# NCV1117STAT3G.net
KiCad netlist of a schematic drawn in Altium Designer
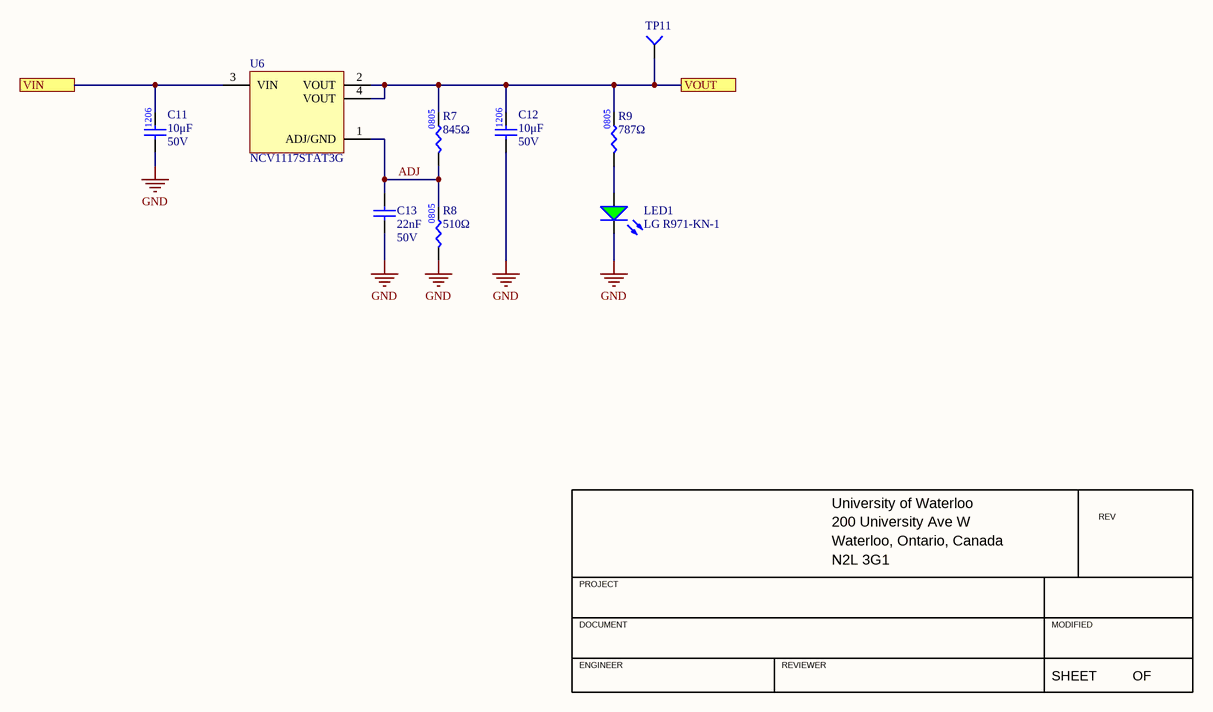
[diagram p0: NCV1117STAT3G.SchDoc]

(export (version "E")
  (design (tool "Eeschema 10.0.6"))
  (components
    (comp (ref "C11")
      (value "10μF")
      (footprint "CAP1206")
      (description "CAP CER 10UF 50V X5R 1206")
      (fields (field (name "VOLTAGE RATING") "50V") (field (name "Comment") "CAP_10uF_50V_1206"))
      (libsource (lib "UWRT_Schematic_Library_2020") (part "CAP_10uF_50V_1206"))
    )
    (comp (ref "C12")
      (value "10μF")
      (footprint "CAP1206")
      (description "CAP CER 10UF 50V X5R 1206")
      (fields (field (name "VOLTAGE RATING") "50V") (field (name "Comment") "CAP_10uF_50V_1206"))
      (libsource (lib "UWRT_Schematic_Library_2020") (part "CAP_10uF_50V_1206"))
    )
    (comp (ref "C13")
      (value "22nF")
      (footprint "CAP0805")
      (description "CAP CER 0.022UF 50V C0G 0805")
      (fields
        (field (name "LCSC PART #") "C1729")
        (field (name "VOLTAGE RATING") "50V")
        (field (name "Comment") "CAP_0.022uF_50V_0805")
      )
      (libsource (lib "UWRT_Schematic_Library_2020") (part "CAP_0.022uF_50V_0805"))
    )
    (comp (ref "LED1")
      (value "LED_GREEN")
      (footprint "LED_0805_GREEN")
      (description "LED GREEN DIFFUSED 0805 SMD")
      (fields (field (name "MANUFACTURER PART NUMBER 1") "LG R971-KN-1"))
      (libsource (lib "UWRT_Schematic_Library_2020") (part "LED_GREEN"))
    )
    (comp (ref "R7")
      (value "845Ω")
      (footprint "RES0805")
      (description "RES 845 OHM 1% 1/8W 0805")
      (fields (field (name "POWER") "0.125W, 1/8W") (field (name "TOLERANCE") "1%"))
      (libsource (lib "UWRT_Schematic_Library_2020") (part "RES_845Ω_0805_1%"))
    )
    (comp (ref "R8")
      (value "510Ω")
      (footprint "RES0805")
      (description "RES 510 OHM 1% 1/8W 0805")
      (fields (field (name "Comment") "RES_510Ω_0805_1%"))
      (libsource (lib "UWRT_Schematic_Library_2020") (part "RES_510Ω_0805_1%"))
    )
    (comp (ref "R9")
      (value "787Ω")
      (footprint "RES0805")
      (description "RES 787 OHM 1% 1/8W 0805")
      (fields (field (name "Comment") "RES_787Ω_0805_1%"))
      (libsource (lib "Personal_Schematic_Library_2022") (part "RES_787Ω_0805_1%"))
    )
    (comp (ref "TP11")
      (value "TESTPOINT_SMD_LOOP")
      (footprint "S1751-46R")
      (description "TESTPOINT SMD LOOP")
      (libsource (lib "UWRT_Schematic_Library_2020") (part "TESTPOINT_SMD_LOOP"))
    )
    (comp (ref "U6")
      (value "LDO_ADJ_1A")
      (footprint "SOT223")
      (description "IC REG LINEAR POS ADJ 1A SOT223")
      (fields (field (name "MANUFACTURER PART NUMBER 1") "NCV1117STAT3G"))
      (libsource (lib "UWRT_Schematic_Library_2020") (part "LDO_ADJ_1A"))
    )
  )
  (nets
    (net (code "1") (name "/ADJ") (class "Default")
      (node (ref "C13") (pin "2") (pinfunction "2_2") (pintype "passive"))
      (node (ref "R7") (pin "1") (pinfunction "1_1") (pintype "passive"))
      (node (ref "R8") (pin "2") (pinfunction "2_2") (pintype "passive"))
      (node (ref "U6") (pin "1") (pinfunction "ADJ/GND_1") (pintype "passive"))
    )
    (net (code "2") (name "/VIN") (class "Default")
      (node (ref "C11") (pin "2") (pinfunction "2_2") (pintype "passive"))
      (node (ref "U6") (pin "3") (pinfunction "VIN_3") (pintype "power_in"))
    )
    (net (code "3") (name "/VOUT") (class "Default")
      (node (ref "C12") (pin "2") (pinfunction "2_2") (pintype "passive"))
      (node (ref "R7") (pin "2") (pinfunction "2_2") (pintype "passive"))
      (node (ref "R9") (pin "2") (pinfunction "2_2") (pintype "passive"))
      (node (ref "TP11") (pin "1") (pinfunction "=value_1") (pintype "passive"))
      (node (ref "U6") (pin "2") (pinfunction "VOUT_2") (pintype "power_in"))
      (node (ref "U6") (pin "4") (pinfunction "VOUT_4") (pintype "power_in"))
    )
    (net (code "4") (name "GND") (class "Default")
      (node (ref "C11") (pin "1") (pinfunction "1_1") (pintype "passive"))
      (node (ref "C12") (pin "1") (pinfunction "1_1") (pintype "passive"))
      (node (ref "C13") (pin "1") (pinfunction "1_1") (pintype "passive"))
      (node (ref "LED1") (pin "2") (pinfunction "K_2") (pintype "passive"))
      (node (ref "R8") (pin "1") (pinfunction "1_1") (pintype "passive"))
    )
    (net (code "5") (name "Net-(LED1-A)") (class "Default")
      (node (ref "LED1") (pin "1") (pinfunction "A_1") (pintype "passive"))
      (node (ref "R9") (pin "1") (pinfunction "1_1") (pintype "passive"))
    )
  )
)
